# Bluetooth_interface_-_RN42.net
KiCad netlist of a schematic drawn in Altium Designer
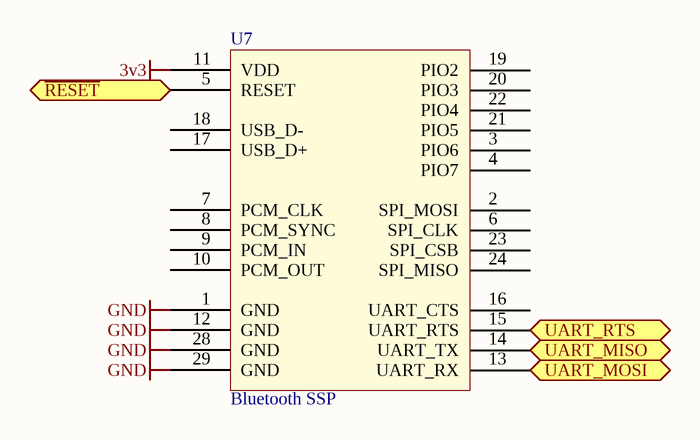
[diagram p0: Bluetooth interface - RN42.SchDoc]

(export (version "E")
  (design (tool "Eeschema 10.0.6"))
  (components
    (comp (ref "U7")
      (value "Bluetooth SSP")
      (footprint "BlueTooth_RN4x")
      (description "Wireless, Bluetooth")
      (fields (field (name "PART NUMBER") "BlueTooth-RN42"))
      (libsource (lib "OurDb") (part "Bluetooth-RN42SMD"))
    )
  )
  (nets
    (net (code "1") (name "/UART_MISO") (class "Default")
      (node (ref "U7") (pin "14") (pinfunction "UART_TX_14") (pintype "passive"))
    )
    (net (code "2") (name "/UART_MOSI") (class "Default")
      (node (ref "U7") (pin "13") (pinfunction "UART_RX_13") (pintype "passive"))
    )
    (net (code "3") (name "/UART_RTS") (class "Default")
      (node (ref "U7") (pin "15") (pinfunction "UART_RTS_15") (pintype "passive"))
    )
    (net (code "4") (name "/~{RESET}") (class "Default")
      (node (ref "U7") (pin "5") (pinfunction "RESET_5") (pintype "passive"))
    )
    (net (code "5") (name "3v3") (class "Default")
      (node (ref "U7") (pin "11") (pinfunction "VDD_11") (pintype "passive"))
    )
    (net (code "6") (name "GND") (class "Default")
      (node (ref "U7") (pin "1") (pinfunction "GND_1") (pintype "passive"))
      (node (ref "U7") (pin "12") (pinfunction "GND_12") (pintype "passive"))
      (node (ref "U7") (pin "28") (pinfunction "GND_28") (pintype "passive"))
      (node (ref "U7") (pin "29") (pinfunction "GND_29") (pintype "passive"))
    )
    (net (code "7") (name "unconnected-(U7-PCM_CLK-Pad7)") (class "Default")
      (node (ref "U7") (pin "7") (pinfunction "PCM_CLK_7") (pintype "passive"))
    )
    (net (code "8") (name "unconnected-(U7-PCM_IN-Pad9)") (class "Default")
      (node (ref "U7") (pin "9") (pinfunction "PCM_IN_9") (pintype "passive"))
    )
    (net (code "9") (name "unconnected-(U7-PCM_OUT-Pad10)") (class "Default")
      (node (ref "U7") (pin "10") (pinfunction "PCM_OUT_10") (pintype "passive"))
    )
    (net (code "10") (name "unconnected-(U7-PCM_SYNC-Pad8)") (class "Default")
      (node (ref "U7") (pin "8") (pinfunction "PCM_SYNC_8") (pintype "passive"))
    )
    (net (code "11") (name "unconnected-(U7-PIO2-Pad19)") (class "Default")
      (node (ref "U7") (pin "19") (pinfunction "PIO2_19") (pintype "passive"))
    )
    (net (code "12") (name "unconnected-(U7-PIO3-Pad20)") (class "Default")
      (node (ref "U7") (pin "20") (pinfunction "PIO3_20") (pintype "passive"))
    )
    (net (code "13") (name "unconnected-(U7-PIO4-Pad22)") (class "Default")
      (node (ref "U7") (pin "22") (pinfunction "PIO4_22") (pintype "passive"))
    )
    (net (code "14") (name "unconnected-(U7-PIO5-Pad21)") (class "Default")
      (node (ref "U7") (pin "21") (pinfunction "PIO5_21") (pintype "passive"))
    )
    (net (code "15") (name "unconnected-(U7-PIO6-Pad3)") (class "Default")
      (node (ref "U7") (pin "3") (pinfunction "PIO6_3") (pintype "passive"))
    )
    (net (code "16") (name "unconnected-(U7-PIO7-Pad4)") (class "Default")
      (node (ref "U7") (pin "4") (pinfunction "PIO7_4") (pintype "passive"))
    )
    (net (code "17") (name "unconnected-(U7-SPI_CLK-Pad6)") (class "Default")
      (node (ref "U7") (pin "6") (pinfunction "SPI_CLK_6") (pintype "passive"))
    )
    (net (code "18") (name "unconnected-(U7-SPI_CSB-Pad23)") (class "Default")
      (node (ref "U7") (pin "23") (pinfunction "SPI_CSB_23") (pintype "passive"))
    )
    (net (code "19") (name "unconnected-(U7-SPI_MISO-Pad24)") (class "Default")
      (node (ref "U7") (pin "24") (pinfunction "SPI_MISO_24") (pintype "passive"))
    )
    (net (code "20") (name "unconnected-(U7-SPI_MOSI-Pad2)") (class "Default")
      (node (ref "U7") (pin "2") (pinfunction "SPI_MOSI_2") (pintype "passive"))
    )
    (net (code "21") (name "unconnected-(U7-UART_CTS-Pad16)") (class "Default")
      (node (ref "U7") (pin "16") (pinfunction "UART_CTS_16") (pintype "passive"))
    )
    (net (code "22") (name "unconnected-(U7-USB_D+-Pad17)") (class "Default")
      (node (ref "U7") (pin "17") (pinfunction "USB_D+_17") (pintype "passive"))
    )
    (net (code "23") (name "unconnected-(U7-USB_D--Pad18)") (class "Default")
      (node (ref "U7") (pin "18") (pinfunction "USB_D-_18") (pintype "passive"))
    )
  )
)
